# TTFT_1_8.net
KiCad netlist of a schematic drawn in Altium Designer
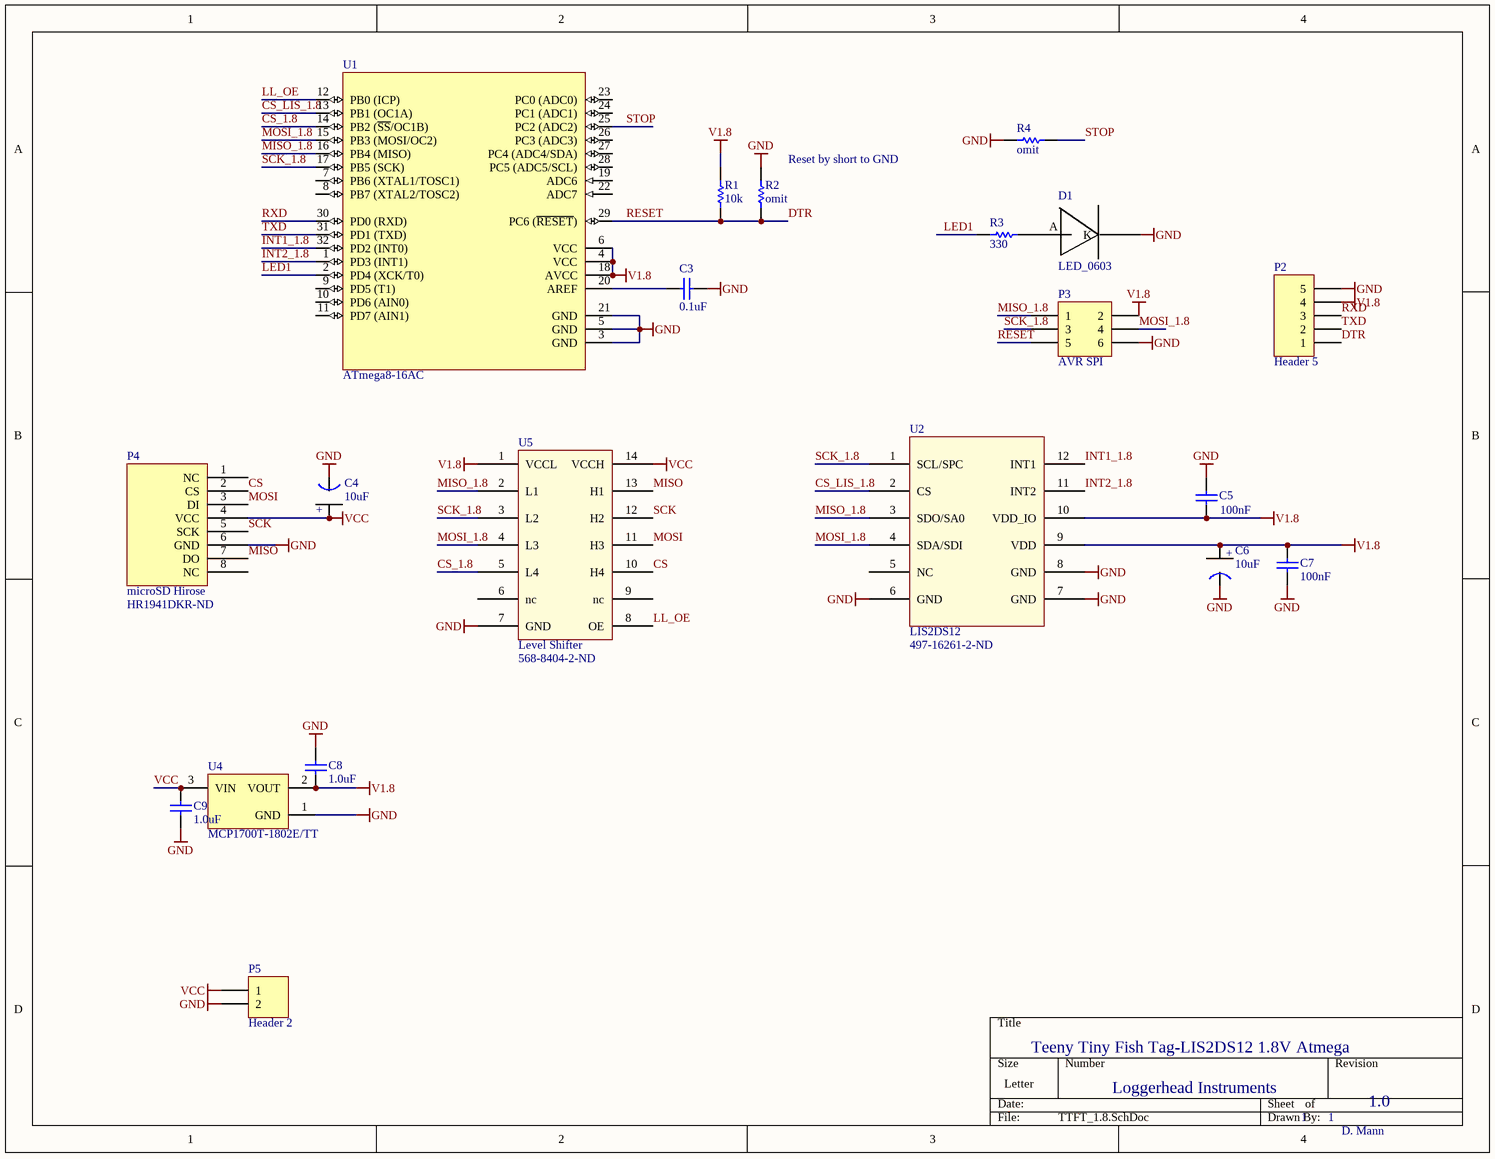
[diagram p0: TTFT_1.8.SchDoc]

(export (version "E")
  (design (tool "Eeschema 10.0.6"))
  (components
    (comp (ref "C3")
      (value "0.1uF")
      (footprint "0402")
      (description "Ceramic Chip Capacitor - Standard")
      (fields (field (name "PUBLISHER") "Altium Limited"))
      (libsource (lib "KEMET Chip Capacitor") (part "C0402"))
    )
    (comp (ref "C4") (value "10uF") (footprint "Tant0805") (libsource (lib "Loggerhead") (part "Tant0805")))
    (comp (ref "C5")
      (value "100nF")
      (footprint "0402")
      (description "Ceramic Chip Capacitor - Standard")
      (fields (field (name "PUBLISHER") "Altium Limited"))
      (libsource (lib "KEMET Chip Capacitor") (part "C0402"))
    )
    (comp (ref "C6") (value "10uF") (footprint "Tant0805") (libsource (lib "Loggerhead") (part "Tant0805")))
    (comp (ref "C7")
      (value "100nF")
      (footprint "0402")
      (description "Ceramic Chip Capacitor - Standard")
      (fields (field (name "PUBLISHER") "Altium Limited"))
      (libsource (lib "KEMET Chip Capacitor") (part "C0402"))
    )
    (comp (ref "C8")
      (value "1.0uF")
      (footprint "0402")
      (description "Ceramic Chip Capacitor - Standard")
      (fields (field (name "PUBLISHER") "Altium Limited"))
      (libsource (lib "KEMET Chip Capacitor") (part "C0402"))
    )
    (comp (ref "C9")
      (value "1.0uF")
      (footprint "0402")
      (description "Ceramic Chip Capacitor - Standard")
      (fields (field (name "PUBLISHER") "Altium Limited"))
      (libsource (lib "KEMET Chip Capacitor") (part "C0402"))
    )
    (comp (ref "D1")
      (value "LED_0603")
      (footprint "Diode0603")
      (libsource (lib "Loggerhead") (part "LED_0603"))
    )
    (comp (ref "P2")
      (value "Header 5")
      (footprint "HDR1X5")
      (description "Header, 5-Pin")
      (fields (field (name "PUBLISHER") "Altium Limited"))
      (libsource (lib "Miscellaneous Connectors") (part "Header 5"))
    )
    (comp (ref "P3")
      (value "AVR SPI")
      (footprint "HDR2X3")
      (description "Header, 3-Pin, Dual row")
      (fields (field (name "PUBLISHER") "Altium Limited"))
      (libsource (lib "Miscellaneous Connectors") (part "Header 3X2"))
    )
    (comp (ref "P4")
      (value "microSD Hirose")
      (footprint "DM3D microSD")
      (fields (field (name "SUPPLIER PART NUMBER 1") "HR1941DKR-ND"))
      (libsource (lib "Loggerhead") (part "microSD Hirose"))
    )
    (comp (ref "P5")
      (value "Header 2")
      (footprint "HDR1X2")
      (description "Header, 2-Pin")
      (fields (field (name "PUBLISHER") "Altium Limited"))
      (libsource (lib "Miscellaneous Connectors") (part "Header 2"))
    )
    (comp (ref "R1")
      (value "10k")
      (footprint "3-0603")
      (fields (field (name "PUBLISHER") "Altium Limited"))
      (libsource (lib "Panasonic Resistor") (part "ERJ3RK"))
    )
    (comp (ref "R2")
      (value "omit")
      (footprint "3-0603")
      (fields (field (name "PUBLISHER") "Altium Limited"))
      (libsource (lib "Panasonic Resistor") (part "ERJ3RK"))
    )
    (comp (ref "R3")
      (value "330")
      (footprint "3-0603")
      (fields (field (name "PUBLISHER") "Altium Limited"))
      (libsource (lib "Panasonic Resistor") (part "ERJ3RK"))
    )
    (comp (ref "R4")
      (value "omit")
      (footprint "3-0603")
      (fields (field (name "PUBLISHER") "Altium Limited"))
      (libsource (lib "Panasonic Resistor") (part "ERJ3RK"))
    )
    (comp (ref "U1")
      (value "ATmega8-16AC")
      (footprint "32M1-A_M")
      (description "8-Bit AVR Microcontroller with 8K Bytes of In-System Programmable Flash Memory")
      (fields (field (name "PUBLISHER") "Altium Limited"))
      (libsource (lib "Atmel Microcontroller 8-Bit AVR") (part "ATmega8-16AC"))
    )
    (comp (ref "U2")
      (value "LIS2DS12")
      (footprint "LGA-12")
      (fields (field (name "SUPPLIER PART NUMBER 1") "497-16261-2-ND"))
      (libsource (lib "Loggerhead") (part "LIS2DS12"))
    )
    (comp (ref "U4")
      (value "MCP1700T-1802E/TT")
      (footprint "SOT-23-TT3_N")
      (description "Low Quiescent Current LDO, 3-Pin SOT-23, Extended Temperature, Tape and Reel")
      (fields (field (name "MANUFACTURER") "Microchip"))
      (libsource (lib "Microchip Power Management Line Regulator") (part "MCP1700T-1802E/TT"))
    )
    (comp (ref "U5")
      (value "Level Shifter")
      (footprint "DHVQFN14")
      (description "Voltage level translator")
      (fields (field (name "SUPPLIER PART NUMBER 1") "568-8404-2-ND"))
      (libsource (lib "Loggerhead") (part "NTB0104"))
    )
  )
  (nets
    (net (code "1") (name "/CS") (class "Default")
      (node (ref "P4") (pin "2") (pinfunction "CS_2") (pintype "passive"))
      (node (ref "U5") (pin "10") (pinfunction "H4_10") (pintype "passive"))
    )
    (net (code "2") (name "/CS_1.8") (class "Default")
      (node (ref "U1") (pin "14") (pinfunction "PB2_(~{SS}/OC1B)_14") (pintype "bidirectional"))
      (node (ref "U5") (pin "5") (pinfunction "L4_5") (pintype "passive"))
    )
    (net (code "3") (name "/CS_LIS_1.8") (class "Default")
      (node (ref "U1") (pin "13") (pinfunction "PB1_(OC1A)_13") (pintype "bidirectional"))
      (node (ref "U2") (pin "2") (pinfunction "CS_2") (pintype "passive"))
    )
    (net (code "4") (name "/DTR") (class "Default")
      (node (ref "P2") (pin "1") (pinfunction "1_1") (pintype "passive"))
      (node (ref "P3") (pin "5") (pinfunction "5_5") (pintype "passive"))
      (node (ref "R1") (pin "1") (pinfunction "1_1") (pintype "passive"))
      (node (ref "R2") (pin "1") (pinfunction "1_1") (pintype "passive"))
      (node (ref "U1") (pin "29") (pinfunction "PC6_(~{RESET})_29") (pintype "bidirectional"))
    )
    (net (code "5") (name "/INT1_1.8") (class "Default")
      (node (ref "U1") (pin "32") (pinfunction "PD2_(INT0)_32") (pintype "bidirectional"))
      (node (ref "U2") (pin "12") (pinfunction "INT1_12") (pintype "passive"))
    )
    (net (code "6") (name "/INT2_1.8") (class "Default")
      (node (ref "U1") (pin "1") (pinfunction "PD3_(INT1)_1") (pintype "bidirectional"))
      (node (ref "U2") (pin "11") (pinfunction "INT2_11") (pintype "passive"))
    )
    (net (code "7") (name "/LED1") (class "Default")
      (node (ref "R3") (pin "1") (pinfunction "1_1") (pintype "passive"))
      (node (ref "U1") (pin "2") (pinfunction "PD4_(XCK/T0)_2") (pintype "bidirectional"))
    )
    (net (code "8") (name "/LL_OE") (class "Default")
      (node (ref "U1") (pin "12") (pinfunction "PB0_(ICP)_12") (pintype "bidirectional"))
      (node (ref "U5") (pin "8") (pinfunction "OE_8") (pintype "passive"))
    )
    (net (code "9") (name "/MISO") (class "Default")
      (node (ref "P4") (pin "7") (pinfunction "DO_7") (pintype "passive"))
      (node (ref "U5") (pin "13") (pinfunction "H1_13") (pintype "passive"))
    )
    (net (code "10") (name "/MISO_1.8") (class "Default")
      (node (ref "P3") (pin "1") (pinfunction "1_1") (pintype "passive"))
      (node (ref "U1") (pin "16") (pinfunction "PB4_(MISO)_16") (pintype "bidirectional"))
      (node (ref "U2") (pin "3") (pinfunction "SDO/SA0_3") (pintype "passive"))
      (node (ref "U5") (pin "2") (pinfunction "L1_2") (pintype "passive"))
    )
    (net (code "11") (name "/MOSI") (class "Default")
      (node (ref "P4") (pin "3") (pinfunction "DI_3") (pintype "passive"))
      (node (ref "U5") (pin "11") (pinfunction "H3_11") (pintype "passive"))
    )
    (net (code "12") (name "/MOSI_1.8") (class "Default")
      (node (ref "P3") (pin "4") (pinfunction "4_4") (pintype "passive"))
      (node (ref "U1") (pin "15") (pinfunction "PB3_(MOSI/OC2)_15") (pintype "bidirectional"))
      (node (ref "U2") (pin "4") (pinfunction "SDA/SDI_4") (pintype "passive"))
      (node (ref "U5") (pin "4") (pinfunction "L3_4") (pintype "passive"))
    )
    (net (code "13") (name "/RXD") (class "Default")
      (node (ref "P2") (pin "3") (pinfunction "3_3") (pintype "passive"))
      (node (ref "U1") (pin "30") (pinfunction "PD0_(RXD)_30") (pintype "bidirectional"))
    )
    (net (code "14") (name "/SCK") (class "Default")
      (node (ref "P4") (pin "5") (pinfunction "SCK_5") (pintype "passive"))
      (node (ref "U5") (pin "12") (pinfunction "H2_12") (pintype "passive"))
    )
    (net (code "15") (name "/SCK_1.8") (class "Default")
      (node (ref "P3") (pin "3") (pinfunction "3_3") (pintype "passive"))
      (node (ref "U1") (pin "17") (pinfunction "PB5_(SCK)_17") (pintype "bidirectional"))
      (node (ref "U2") (pin "1") (pinfunction "SCL/SPC_1") (pintype "passive"))
      (node (ref "U5") (pin "3") (pinfunction "L2_3") (pintype "passive"))
    )
    (net (code "16") (name "/STOP") (class "Default")
      (node (ref "R4") (pin "1") (pinfunction "1_1") (pintype "passive"))
      (node (ref "U1") (pin "25") (pinfunction "PC2_(ADC2)_25") (pintype "bidirectional"))
    )
    (net (code "17") (name "/TXD") (class "Default")
      (node (ref "P2") (pin "2") (pinfunction "2_2") (pintype "passive"))
      (node (ref "U1") (pin "31") (pinfunction "PD1_(TXD)_31") (pintype "bidirectional"))
    )
    (net (code "18") (name "GND") (class "Default")
      (node (ref "C3") (pin "2") (pinfunction "2_2") (pintype "passive"))
      (node (ref "C4") (pin "1") (pinfunction "GND_1") (pintype "passive"))
      (node (ref "C5") (pin "2") (pinfunction "2_2") (pintype "passive"))
      (node (ref "C6") (pin "1") (pinfunction "GND_1") (pintype "passive"))
      (node (ref "C7") (pin "2") (pinfunction "2_2") (pintype "passive"))
      (node (ref "C8") (pin "2") (pinfunction "2_2") (pintype "passive"))
      (node (ref "C9") (pin "2") (pinfunction "2_2") (pintype "passive"))
      (node (ref "D1") (pin "K") (pinfunction "K_K") (pintype "passive"))
      (node (ref "P2") (pin "5") (pinfunction "5_5") (pintype "passive"))
      (node (ref "P3") (pin "6") (pinfunction "6_6") (pintype "passive"))
      (node (ref "P4") (pin "6") (pinfunction "GND_6") (pintype "passive"))
      (node (ref "P5") (pin "2") (pinfunction "2_2") (pintype "passive"))
      (node (ref "R2") (pin "2") (pinfunction "2_2") (pintype "passive"))
      (node (ref "R4") (pin "2") (pinfunction "2_2") (pintype "passive"))
      (node (ref "U1") (pin "21") (pinfunction "GND_21") (pintype "power_in"))
      (node (ref "U1") (pin "3") (pinfunction "GND_3") (pintype "power_in"))
      (node (ref "U1") (pin "5") (pinfunction "GND_5") (pintype "power_in"))
      (node (ref "U2") (pin "6") (pinfunction "GND_6") (pintype "passive"))
      (node (ref "U2") (pin "7") (pinfunction "GND_7") (pintype "passive"))
      (node (ref "U2") (pin "8") (pinfunction "GND_8") (pintype "passive"))
      (node (ref "U4") (pin "1") (pinfunction "GND_1") (pintype "power_in"))
      (node (ref "U5") (pin "7") (pinfunction "GND_7") (pintype "passive"))
    )
    (net (code "19") (name "Net-(D1-PadA)") (class "Default")
      (node (ref "D1") (pin "A") (pinfunction "A_A") (pintype "passive"))
      (node (ref "R3") (pin "2") (pinfunction "2_2") (pintype "passive"))
    )
    (net (code "20") (name "Net-(U1-AREF)") (class "Default")
      (node (ref "C3") (pin "1") (pinfunction "1_1") (pintype "passive"))
      (node (ref "U1") (pin "20") (pinfunction "AREF_20") (pintype "passive"))
    )
    (net (code "21") (name "V1.8") (class "Default")
      (node (ref "C5") (pin "1") (pinfunction "1_1") (pintype "passive"))
      (node (ref "C6") (pin "2") (pinfunction "+_2") (pintype "passive"))
      (node (ref "C7") (pin "1") (pinfunction "1_1") (pintype "passive"))
      (node (ref "C8") (pin "1") (pinfunction "1_1") (pintype "passive"))
      (node (ref "P2") (pin "4") (pinfunction "4_4") (pintype "passive"))
      (node (ref "P3") (pin "2") (pinfunction "2_2") (pintype "passive"))
      (node (ref "R1") (pin "2") (pinfunction "2_2") (pintype "passive"))
      (node (ref "U1") (pin "18") (pinfunction "AVCC_18") (pintype "power_in"))
      (node (ref "U1") (pin "4") (pinfunction "VCC_4") (pintype "power_in"))
      (node (ref "U1") (pin "6") (pinfunction "VCC_6") (pintype "power_in"))
      (node (ref "U2") (pin "10") (pinfunction "VDD_IO_10") (pintype "passive"))
      (node (ref "U2") (pin "9") (pinfunction "VDD_9") (pintype "passive"))
      (node (ref "U4") (pin "2") (pinfunction "VOUT_2") (pintype "power_in"))
      (node (ref "U5") (pin "1") (pinfunction "VCCL_1") (pintype "passive"))
    )
    (net (code "22") (name "VCC") (class "Default")
      (node (ref "C4") (pin "2") (pinfunction "+_2") (pintype "passive"))
      (node (ref "C9") (pin "1") (pinfunction "1_1") (pintype "passive"))
      (node (ref "P4") (pin "4") (pinfunction "VCC_4") (pintype "passive"))
      (node (ref "P5") (pin "1") (pinfunction "1_1") (pintype "passive"))
      (node (ref "U4") (pin "3") (pinfunction "VIN_3") (pintype "power_in"))
      (node (ref "U5") (pin "14") (pinfunction "VCCH_14") (pintype "passive"))
    )
    (net (code "23") (name "unconnected-(P4-NC-Pad1)") (class "Default")
      (node (ref "P4") (pin "1") (pinfunction "NC_1") (pintype "passive"))
    )
    (net (code "24") (name "unconnected-(P4-NC-Pad8)") (class "Default")
      (node (ref "P4") (pin "8") (pinfunction "NC_8") (pintype "passive"))
    )
    (net (code "25") (name "unconnected-(U1-ADC6-Pad19)") (class "Default")
      (node (ref "U1") (pin "19") (pinfunction "ADC6_19") (pintype "input"))
    )
    (net (code "26") (name "unconnected-(U1-ADC7-Pad22)") (class "Default")
      (node (ref "U1") (pin "22") (pinfunction "ADC7_22") (pintype "input"))
    )
    (net (code "27") (name "unconnected-(U1-PB6_(XTAL1{slash}TOSC1)-Pad7)") (class "Default")
      (node (ref "U1") (pin "7") (pinfunction "PB6_(XTAL1/TOSC1)_7") (pintype "bidirectional"))
    )
    (net (code "28") (name "unconnected-(U1-PB7_(XTAL2{slash}TOSC2)-Pad8)") (class "Default")
      (node (ref "U1") (pin "8") (pinfunction "PB7_(XTAL2/TOSC2)_8") (pintype "bidirectional"))
    )
    (net (code "29") (name "unconnected-(U1-PC0_(ADC0)-Pad23)") (class "Default")
      (node (ref "U1") (pin "23") (pinfunction "PC0_(ADC0)_23") (pintype "bidirectional"))
    )
    (net (code "30") (name "unconnected-(U1-PC1_(ADC1)-Pad24)") (class "Default")
      (node (ref "U1") (pin "24") (pinfunction "PC1_(ADC1)_24") (pintype "bidirectional"))
    )
    (net (code "31") (name "unconnected-(U1-PC3_(ADC3)-Pad26)") (class "Default")
      (node (ref "U1") (pin "26") (pinfunction "PC3_(ADC3)_26") (pintype "bidirectional"))
    )
    (net (code "32") (name "unconnected-(U1-PC4_(ADC4{slash}SDA)-Pad27)") (class "Default")
      (node (ref "U1") (pin "27") (pinfunction "PC4_(ADC4/SDA)_27") (pintype "bidirectional"))
    )
    (net (code "33") (name "unconnected-(U1-PC5_(ADC5{slash}SCL)-Pad28)") (class "Default")
      (node (ref "U1") (pin "28") (pinfunction "PC5_(ADC5/SCL)_28") (pintype "bidirectional"))
    )
    (net (code "34") (name "unconnected-(U1-PD5_(T1)-Pad9)") (class "Default")
      (node (ref "U1") (pin "9") (pinfunction "PD5_(T1)_9") (pintype "bidirectional"))
    )
    (net (code "35") (name "unconnected-(U1-PD6_(AIN0)-Pad10)") (class "Default")
      (node (ref "U1") (pin "10") (pinfunction "PD6_(AIN0)_10") (pintype "bidirectional"))
    )
    (net (code "36") (name "unconnected-(U1-PD7_(AIN1)-Pad11)") (class "Default")
      (node (ref "U1") (pin "11") (pinfunction "PD7_(AIN1)_11") (pintype "bidirectional"))
    )
    (net (code "37") (name "unconnected-(U2-NC-Pad5)") (class "Default")
      (node (ref "U2") (pin "5") (pinfunction "NC_5") (pintype "passive"))
    )
    (net (code "38") (name "unconnected-(U5-nc-Pad6)") (class "Default")
      (node (ref "U5") (pin "6") (pinfunction "nc_6") (pintype "passive"))
    )
    (net (code "39") (name "unconnected-(U5-nc-Pad9)") (class "Default")
      (node (ref "U5") (pin "9") (pinfunction "nc_9") (pintype "passive"))
    )
  )
)
